# version_3.net
KiCad netlist of a schematic drawn in EAGLE
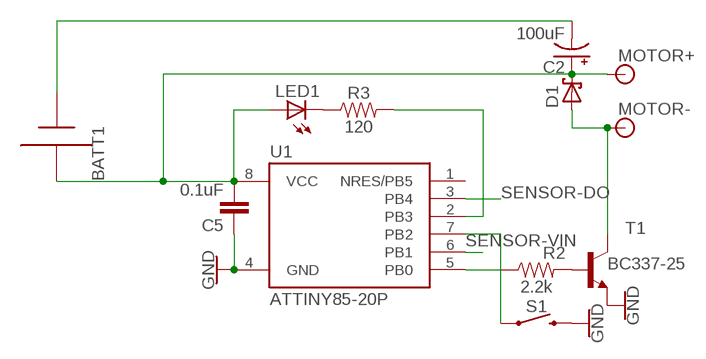
[diagram p0: schematic, sheet 1]

(export (version "E")
  (design (tool "Eeschema 10.0.6"))
  (components
    (comp (ref "BATT1")
      (value "AAA")
      (footprint "eagle-import:12BH412")
      (libsource (lib "eagle-import") (part "AAA"))
    )
    (comp (ref "C2")
      (value "100uF")
      (footprint "eagle-import:0603-POLAR")
      (libsource (lib "eagle-import") (part "10UF-POLAR-0603-6.3V-20%(TANT)"))
    )
    (comp (ref "C5")
      (value "0.1uF")
      (footprint "eagle-import:CAP-PTH-SMALL-KIT")
      (libsource (lib "eagle-import") (part "0.1UF-KIT-EZ-50V-20%"))
    )
    (comp (ref "D1")
      (value "SCHOTTKY-DIODEAG")
      (footprint "eagle-import:AG")
      (libsource (lib "eagle-import") (part "SCHOTTKY-DIODEAG"))
    )
    (comp (ref "LED1")
      (value "LED3MM")
      (footprint "eagle-import:LED3MM")
      (libsource (lib "eagle-import") (part "LED3MM"))
    )
    (comp (ref "MOTOR+")
      (value "BANANA_CONN")
      (footprint "eagle-import:BANANA_CONN")
      (libsource (lib "eagle-import") (part "BANANA_CONN"))
    )
    (comp (ref "MOTOR-")
      (value "BANANA_CONN")
      (footprint "eagle-import:BANANA_CONN")
      (libsource (lib "eagle-import") (part "BANANA_CONN"))
    )
    (comp (ref "R2")
      (value "2.2k")
      (footprint "eagle-import:0603")
      (libsource (lib "eagle-import") (part "2.2KOHM-0603-1/10W-1%"))
    )
    (comp (ref "R3")
      (value "120")
      (footprint "eagle-import:AXIAL-0.3")
      (libsource (lib "eagle-import") (part "100OHM-HORIZ-1/4W-1%"))
    )
    (comp (ref "S1")
      (value "MOMENTARY-SWITCH-SPST-PTH-6.0MM")
      (footprint "eagle-import:TACTILE_SWITCH_PTH_6.0MM")
      (libsource (lib "eagle-import") (part "MOMENTARY-SWITCH-SPST-PTH-6.0MM"))
    )
    (comp (ref "T1")
      (value "2N2222")
      (footprint "eagle-import:TO92-EBC-OVAL")
      (fields (field (name "MODEL") "BC337-25"))
      (libsource (lib "eagle-import") (part "2N2222"))
    )
    (comp (ref "U1")
      (value "ATTINY85-20P")
      (footprint "eagle-import:PDIP08_300MIL")
      (libsource (lib "eagle-import") (part "ATTINY85P-20"))
    )
  )
  (nets
    (net (code "1") (name "/SENSOR-DO") (class "Default")
      (node (ref "U1") (pin "3") (pinfunction "PB4_3") (pintype "bidirectional"))
    )
    (net (code "2") (name "/SENSOR-VIN") (class "Default")
      (node (ref "U1") (pin "6") (pinfunction "PB1_6") (pintype "bidirectional"))
    )
    (net (code "3") (name "GND") (class "Default")
      (node (ref "C5") (pin "1") (pinfunction "1_1") (pintype "passive"))
      (node (ref "S1") (pin "3") (pinfunction "2_3") (pintype "passive"))
      (node (ref "T1") (pin "E") (pinfunction "E_E") (pintype "passive"))
      (node (ref "U1") (pin "4") (pinfunction "GND_4") (pintype "power_in"))
    )
    (net (code "4") (name "Net-(BATT1-Pad+)") (class "Default")
      (node (ref "BATT1") (pin "+") (pinfunction "+_+") (pintype "bidirectional"))
      (node (ref "C2") (pin "-") (pinfunction "-_-") (pintype "passive"))
    )
    (net (code "5") (name "Net-(LED1-C)") (class "Default")
      (node (ref "LED1") (pin "K") (pinfunction "C_K") (pintype "passive"))
      (node (ref "R3") (pin "P$1") (pinfunction "1_P$1") (pintype "passive"))
    )
    (net (code "6") (name "Net-(MOTOR+-1)") (class "Default")
      (node (ref "BATT1") (pin "-") (pinfunction "-_-") (pintype "bidirectional"))
      (node (ref "C2") (pin "+") (pinfunction "+_+") (pintype "passive"))
      (node (ref "C5") (pin "2") (pinfunction "2_2") (pintype "passive"))
      (node (ref "D1") (pin "C") (pinfunction "C_C") (pintype "passive"))
      (node (ref "LED1") (pin "A") (pinfunction "A_A") (pintype "passive"))
      (node (ref "MOTOR+") (pin "P$1") (pinfunction "1_P$1") (pintype "passive"))
      (node (ref "U1") (pin "8") (pinfunction "VCC_8") (pintype "power_in"))
    )
    (net (code "7") (name "Net-(MOTOR--1)") (class "Default")
      (node (ref "D1") (pin "A") (pinfunction "A_A") (pintype "passive"))
      (node (ref "MOTOR-") (pin "P$1") (pinfunction "1_P$1") (pintype "passive"))
      (node (ref "T1") (pin "C") (pinfunction "C_C") (pintype "passive"))
    )
    (net (code "8") (name "Net-(R2-Pad2)") (class "Default")
      (node (ref "R2") (pin "2") (pinfunction "2_2") (pintype "passive"))
      (node (ref "T1") (pin "B") (pinfunction "B_B") (pintype "passive"))
    )
    (net (code "9") (name "Net-(R3-2)") (class "Default")
      (node (ref "R3") (pin "P$2") (pinfunction "2_P$2") (pintype "passive"))
      (node (ref "U1") (pin "2") (pinfunction "PB3_2") (pintype "bidirectional"))
    )
    (net (code "10") (name "Net-(U1-PB0)") (class "Default")
      (node (ref "R2") (pin "1") (pinfunction "1_1") (pintype "passive"))
      (node (ref "U1") (pin "5") (pinfunction "PB0_5") (pintype "bidirectional"))
    )
    (net (code "11") (name "Net-(U1-PB2)") (class "Default")
      (node (ref "S1") (pin "1") (pinfunction "1_1") (pintype "passive"))
      (node (ref "U1") (pin "7") (pinfunction "PB2_7") (pintype "bidirectional"))
    )
    (net (code "12") (name "unconnected-(U1-NRES{slash}PB5-Pad1)") (class "Default")
      (node (ref "U1") (pin "1") (pinfunction "NRES/PB5_1") (pintype "bidirectional"))
    )
  )
)
